# DCO_PIGGY.net
KiCad netlist of a schematic drawn in EAGLE
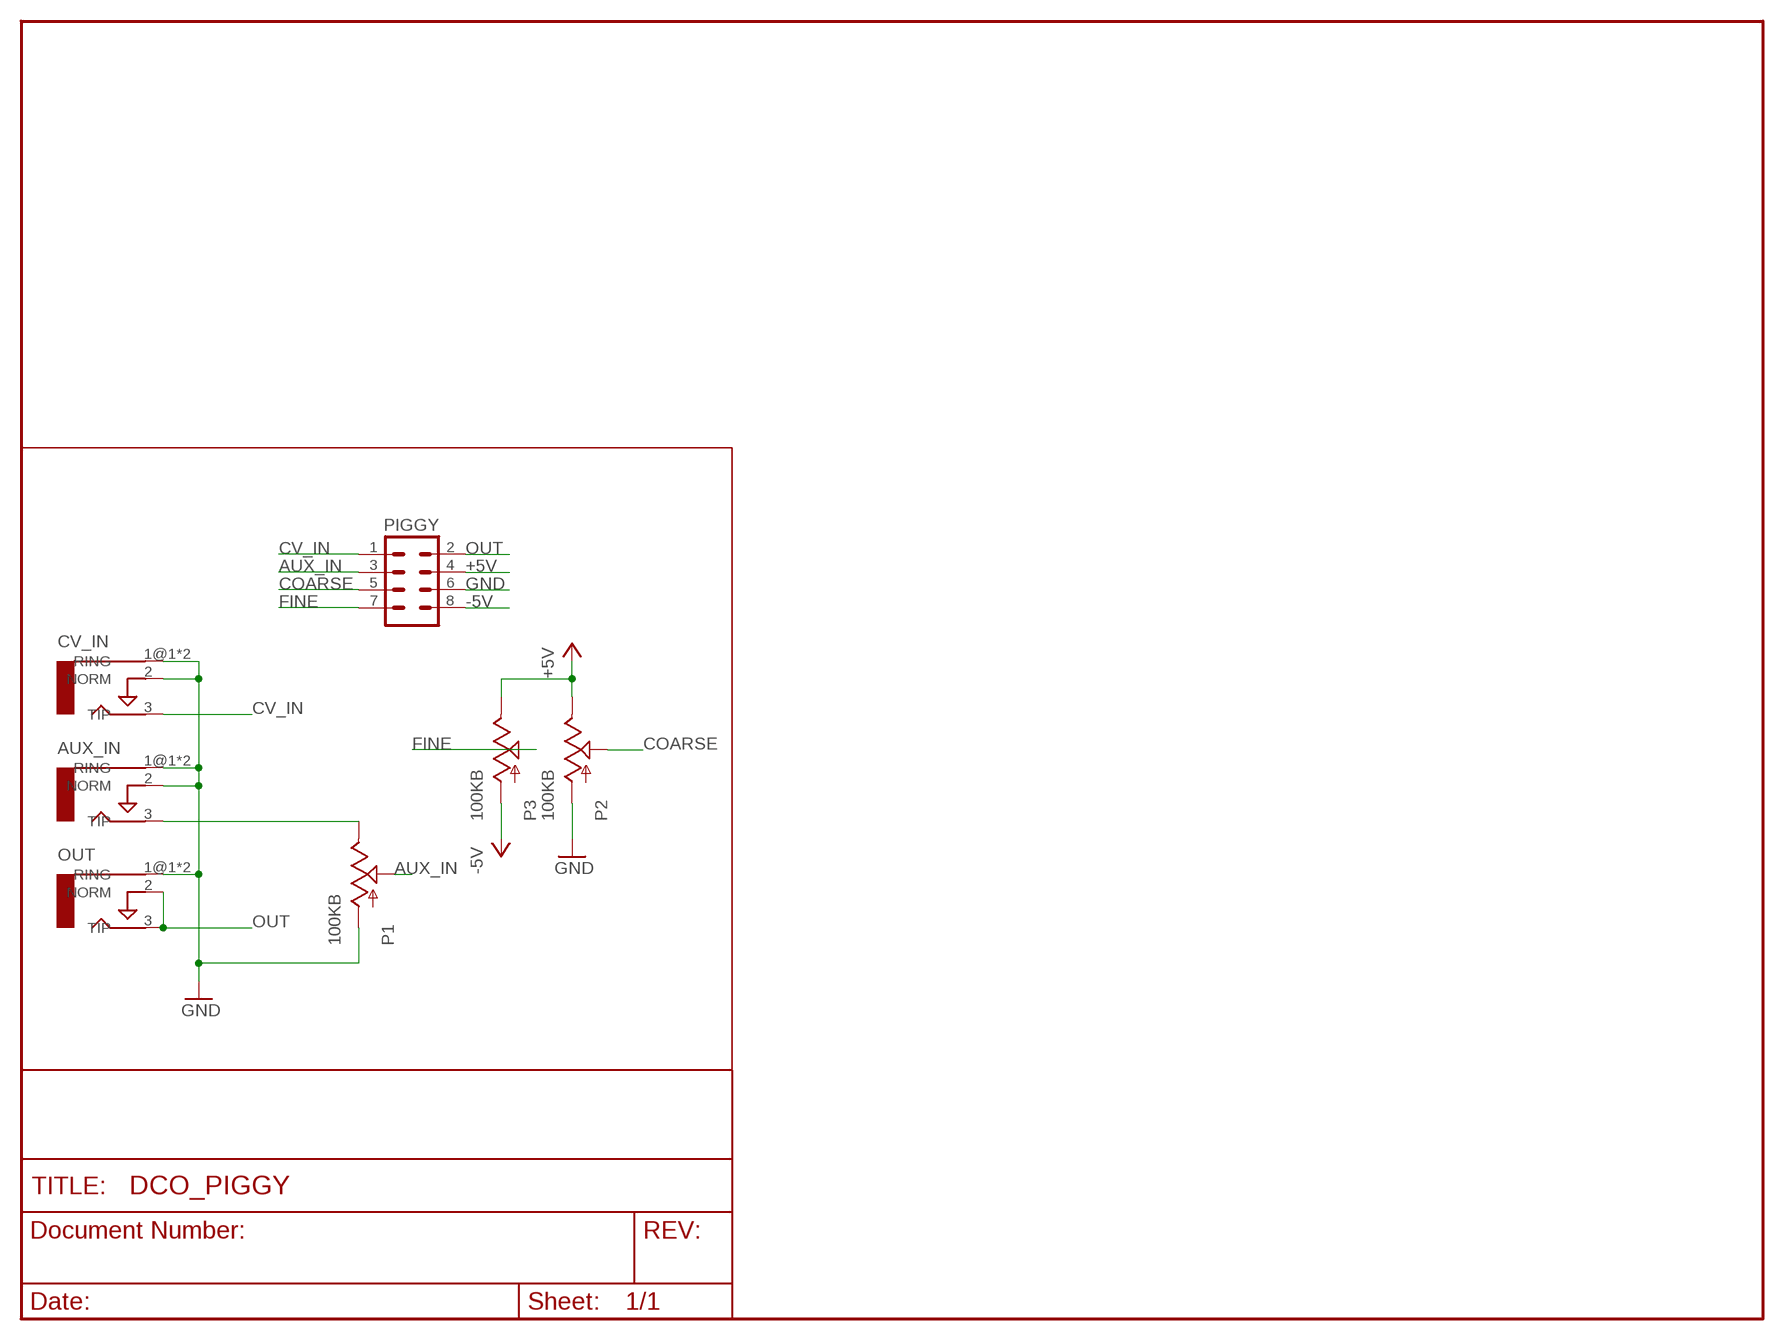
[diagram p0: schematic, sheet 1]

(export (version "E")
  (design (tool "Eeschema 10.0.6"))
  (components
    (comp (ref "AUX_IN")
      (value "AUDIO-JACKERTHENVAR")
      (footprint "eagle-import:ERTHENVAR-JACK")
      (libsource (lib "eagle-import") (part "AUDIO-JACKERTHENVAR"))
    )
    (comp (ref "CV_IN")
      (value "AUDIO-JACKERTHENVAR")
      (footprint "eagle-import:ERTHENVAR-JACK")
      (libsource (lib "eagle-import") (part "AUDIO-JACKERTHENVAR"))
    )
    (comp (ref "OUT")
      (value "AUDIO-JACKERTHENVAR")
      (footprint "eagle-import:ERTHENVAR-JACK")
      (libsource (lib "eagle-import") (part "AUDIO-JACKERTHENVAR"))
    )
    (comp (ref "P1")
      (value "100KB")
      (footprint "eagle-import:PDB12")
      (libsource (lib "eagle-import") (part "POTPDB12"))
    )
    (comp (ref "P2")
      (value "100KB")
      (footprint "eagle-import:PDB12")
      (libsource (lib "eagle-import") (part "POTPDB12"))
    )
    (comp (ref "P3")
      (value "100KB")
      (footprint "eagle-import:PDB12")
      (libsource (lib "eagle-import") (part "POTPDB12"))
    )
    (comp (ref "PIGGY")
      (value "M04X2")
      (footprint "eagle-import:2X4")
      (libsource (lib "eagle-import") (part "M04X2"))
    )
  )
  (nets
    (net (code "1") (name "+5V") (class "Default")
      (node (ref "P2") (pin "3") (pinfunction "E_3") (pintype "passive"))
      (node (ref "P3") (pin "3") (pinfunction "E_3") (pintype "passive"))
      (node (ref "PIGGY") (pin "4") (pinfunction "4_4") (pintype "passive"))
    )
    (net (code "2") (name "-5V") (class "Default")
      (node (ref "P3") (pin "1") (pinfunction "A_1") (pintype "passive"))
      (node (ref "PIGGY") (pin "8") (pinfunction "8_8") (pintype "passive"))
    )
    (net (code "3") (name "/AUX_IN") (class "Default")
      (node (ref "P1") (pin "2") (pinfunction "S_2") (pintype "passive"))
      (node (ref "PIGGY") (pin "3") (pinfunction "3_3") (pintype "passive"))
    )
    (net (code "4") (name "/COARSE") (class "Default")
      (node (ref "P2") (pin "2") (pinfunction "S_2") (pintype "passive"))
      (node (ref "PIGGY") (pin "5") (pinfunction "5_5") (pintype "passive"))
    )
    (net (code "5") (name "/CV_IN") (class "Default")
      (node (ref "CV_IN") (pin "3") (pinfunction "TIP_3") (pintype "bidirectional"))
      (node (ref "PIGGY") (pin "1") (pinfunction "1_1") (pintype "passive"))
    )
    (net (code "6") (name "/FINE") (class "Default")
      (node (ref "P3") (pin "2") (pinfunction "S_2") (pintype "passive"))
      (node (ref "PIGGY") (pin "7") (pinfunction "7_7") (pintype "passive"))
    )
    (net (code "7") (name "/OUT") (class "Default")
      (node (ref "OUT") (pin "2") (pinfunction "NORM_2") (pintype "bidirectional"))
      (node (ref "OUT") (pin "3") (pinfunction "TIP_3") (pintype "bidirectional"))
      (node (ref "PIGGY") (pin "2") (pinfunction "2_2") (pintype "passive"))
    )
    (net (code "8") (name "GND") (class "Default")
      (node (ref "AUX_IN") (pin "1@1") (pinfunction "RING_1@1") (pintype "bidirectional"))
      (node (ref "AUX_IN") (pin "1@2") (pinfunction "RING_1@2") (pintype "bidirectional"))
      (node (ref "AUX_IN") (pin "2") (pinfunction "NORM_2") (pintype "bidirectional"))
      (node (ref "CV_IN") (pin "1@1") (pinfunction "RING_1@1") (pintype "bidirectional"))
      (node (ref "CV_IN") (pin "1@2") (pinfunction "RING_1@2") (pintype "bidirectional"))
      (node (ref "CV_IN") (pin "2") (pinfunction "NORM_2") (pintype "bidirectional"))
      (node (ref "OUT") (pin "1@1") (pinfunction "RING_1@1") (pintype "bidirectional"))
      (node (ref "OUT") (pin "1@2") (pinfunction "RING_1@2") (pintype "bidirectional"))
      (node (ref "P1") (pin "1") (pinfunction "A_1") (pintype "passive"))
      (node (ref "P2") (pin "1") (pinfunction "A_1") (pintype "passive"))
      (node (ref "PIGGY") (pin "6") (pinfunction "6_6") (pintype "passive"))
    )
    (net (code "9") (name "Net-(AUX_IN-TIP)") (class "Default")
      (node (ref "AUX_IN") (pin "3") (pinfunction "TIP_3") (pintype "bidirectional"))
      (node (ref "P1") (pin "3") (pinfunction "E_3") (pintype "passive"))
    )
  )
)
